# unoshield-v6.net
KiCad netlist of a schematic drawn in EAGLE
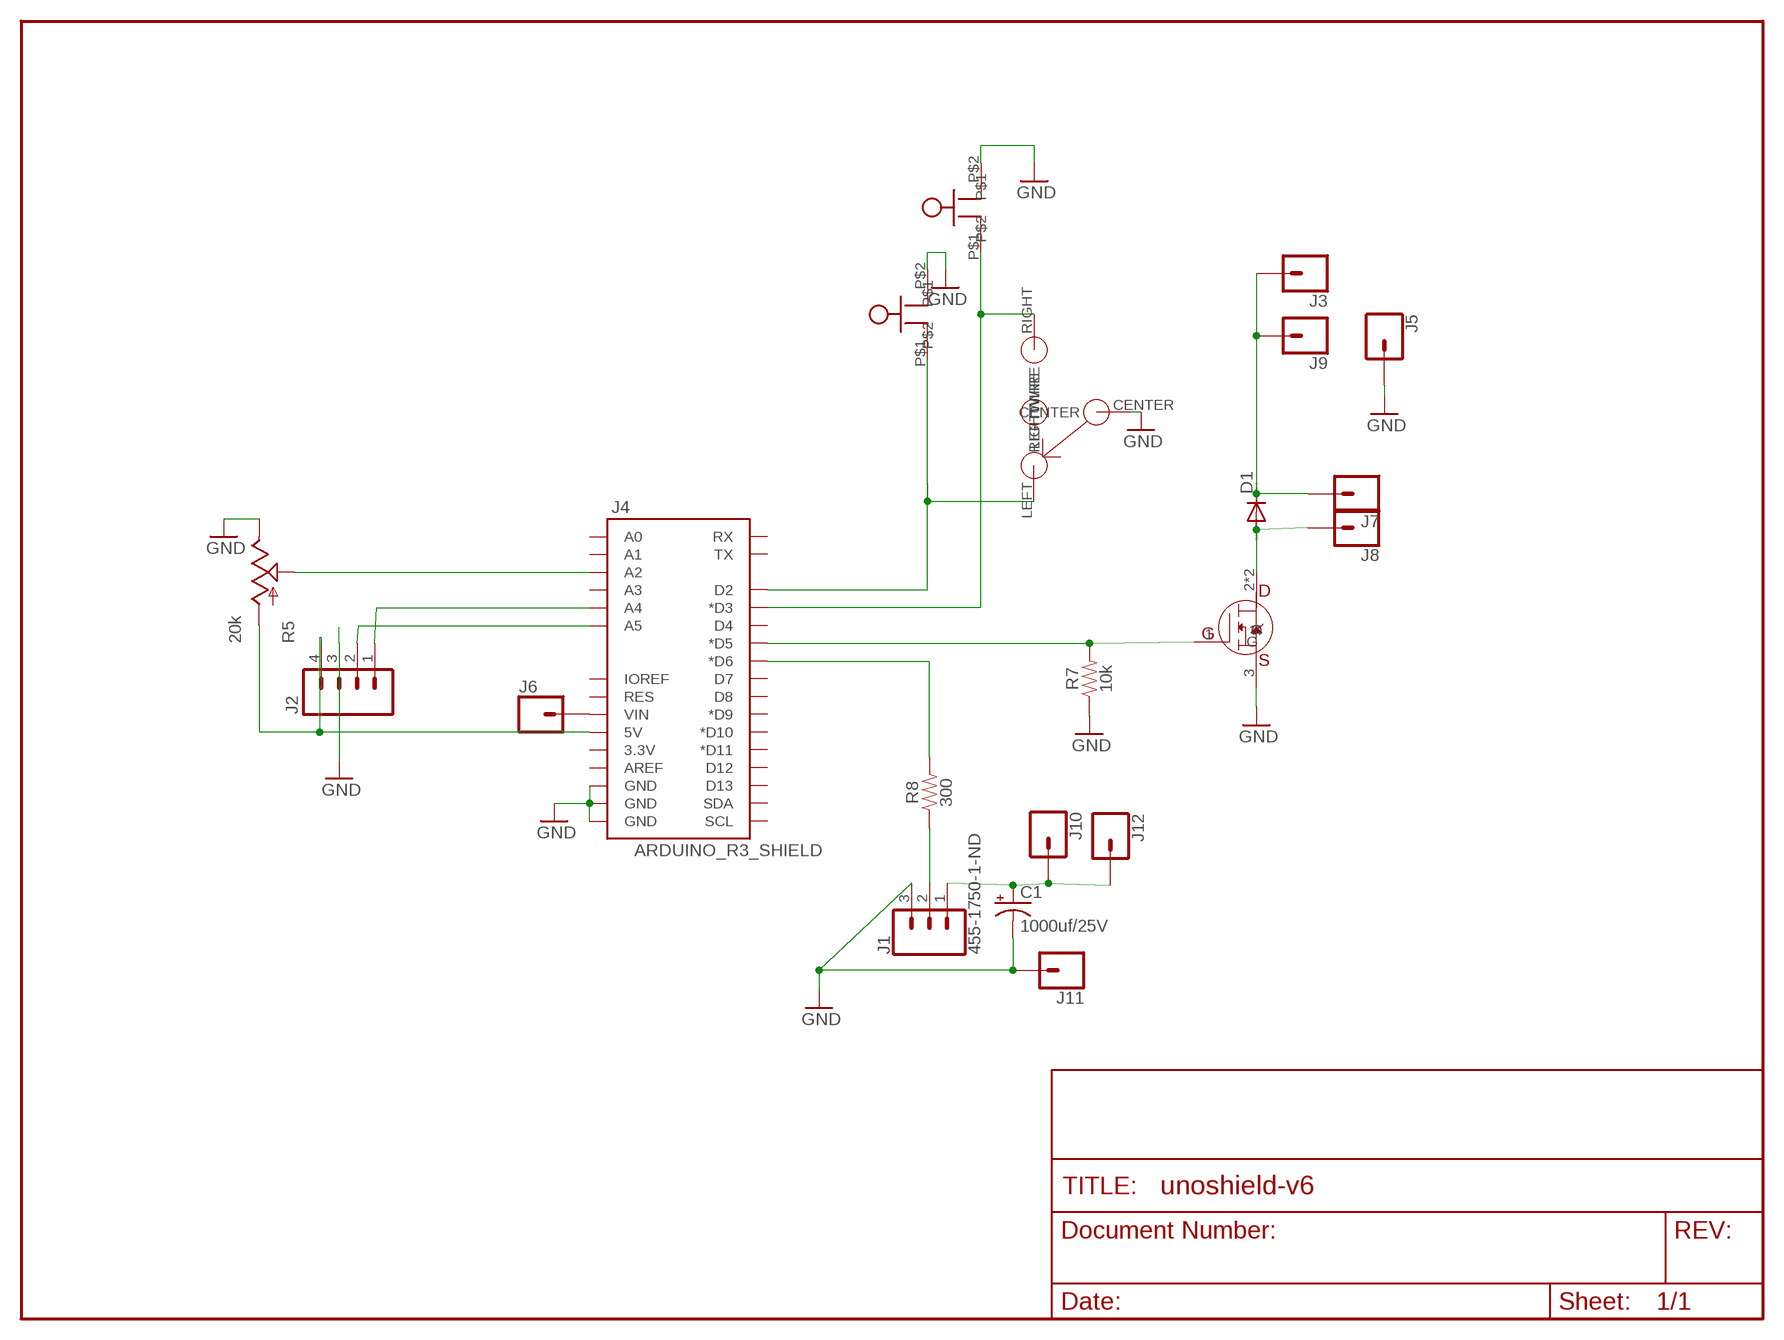
[diagram p0: schematic, sheet 1]

(export (version "E")
  (design (tool "Eeschema 10.0.6"))
  (components
    (comp (ref "C1")
      (value "1000uf/25V")
      (footprint "eagle-import:CPOL-RADIAL-1000UF-25V-KIT")
      (libsource (lib "eagle-import") (part "1000UF-25V(PTH)KIT"))
    )
    (comp (ref "D1")
      (value "DIODE-DO-214AC")
      (footprint "eagle-import:DO-214AC")
      (libsource (lib "eagle-import") (part "DIODE-DO-214AC"))
    )
    (comp (ref "J1")
      (value "455-1750-1-ND")
      (footprint "eagle-import:1X03")
      (libsource (lib "eagle-import") (part "CONN_03"))
    )
    (comp (ref "J2")
      (value "M04PTH")
      (footprint "eagle-import:1X04")
      (libsource (lib "eagle-import") (part "M04PTH"))
    )
    (comp (ref "J3")
      (value "CONN_01PTH_2MM")
      (footprint "eagle-import:1X01_2MM")
      (libsource (lib "eagle-import") (part "CONN_01PTH_2MM"))
    )
    (comp (ref "J4")
      (value "ARDUINO_R3_SHIELD")
      (footprint "eagle-import:UNO_R3_SHIELD")
      (libsource (lib "eagle-import") (part "ARDUINO_R3_SHIELD"))
    )
    (comp (ref "J5")
      (value "CONN_01PTH_2MM")
      (footprint "eagle-import:1X01_2MM")
      (libsource (lib "eagle-import") (part "CONN_01PTH_2MM"))
    )
    (comp (ref "J6")
      (value "CONN_01")
      (footprint "eagle-import:1X01")
      (libsource (lib "eagle-import") (part "CONN_01"))
    )
    (comp (ref "J7")
      (value "CONN_01PTH_2MM")
      (footprint "eagle-import:1X01_2MM")
      (libsource (lib "eagle-import") (part "CONN_01PTH_2MM"))
    )
    (comp (ref "J8")
      (value "CONN_01PTH_2MM")
      (footprint "eagle-import:1X01_2MM")
      (libsource (lib "eagle-import") (part "CONN_01PTH_2MM"))
    )
    (comp (ref "J9")
      (value "CONN_01")
      (footprint "eagle-import:1X01")
      (libsource (lib "eagle-import") (part "CONN_01"))
    )
    (comp (ref "J10")
      (value "CONN_01PTH_2MM")
      (footprint "eagle-import:1X01_2MM")
      (libsource (lib "eagle-import") (part "CONN_01PTH_2MM"))
    )
    (comp (ref "J11")
      (value "CONN_01PTH_2MM")
      (footprint "eagle-import:1X01_2MM")
      (libsource (lib "eagle-import") (part "CONN_01PTH_2MM"))
    )
    (comp (ref "J12")
      (value "CONN_01")
      (footprint "eagle-import:1X01")
      (libsource (lib "eagle-import") (part "CONN_01"))
    )
    (comp (ref "R5")
      (value "20k")
      (footprint "eagle-import:ALPS_POT_KIT")
      (libsource (lib "eagle-import") (part "POTALPS-KIT"))
    )
    (comp (ref "R7")
      (value "10k")
      (footprint "eagle-import:AXIAL-0.3")
      (libsource (lib "eagle-import") (part "10KOHM-HORIZ-1/4W-1%"))
    )
    (comp (ref "R8")
      (value "300")
      (footprint "eagle-import:AXIAL-0.3")
      (libsource (lib "eagle-import") (part "1KOHM-HORIZ-1/4W-5%"))
    )
    (comp (ref "SW1")
      (value "BUTTON")
      (footprint "eagle-import:BUTTON")
      (libsource (lib "eagle-import") (part "BUTTON"))
    )
    (comp (ref "SW2")
      (value "BUTTON")
      (footprint "eagle-import:BUTTON")
      (libsource (lib "eagle-import") (part "BUTTON"))
    )
    (comp (ref "SW3")
      (value "ON-OFF-ON-360-1013-ND")
      (footprint "eagle-import:360-1013-ND")
      (libsource (lib "eagle-import") (part "ON-OFF-ON-360-1013-ND"))
    )
    (comp (ref "U$1")
      (value "IRFL024NPBF")
      (footprint "eagle-import:SOT223")
      (libsource (lib "eagle-import") (part "IRFL024NPBF"))
    )
  )
  (nets
    (net (code "1") (name "GND") (class "Default")
      (node (ref "C1") (pin "-") (pinfunction "-_-") (pintype "passive"))
      (node (ref "J1") (pin "3") (pinfunction "3_3") (pintype "passive"))
      (node (ref "J11") (pin "1") (pinfunction "1_1") (pintype "passive"))
      (node (ref "J2") (pin "3") (pinfunction "3_3") (pintype "passive"))
      (node (ref "J4") (pin "GND@0") (pinfunction "GND_GND@0") (pintype "bidirectional"))
      (node (ref "J4") (pin "GND@1") (pinfunction "GND_GND@1") (pintype "bidirectional"))
      (node (ref "J4") (pin "GND@2") (pinfunction "GND_GND@2") (pintype "bidirectional"))
      (node (ref "J5") (pin "1") (pinfunction "1_1") (pintype "passive"))
      (node (ref "R5") (pin "P$1") (pinfunction "E_P$1") (pintype "passive"))
      (node (ref "R7") (pin "P$1") (pinfunction "1_P$1") (pintype "passive"))
      (node (ref "SW1") (pin "P$2") (pinfunction "P$2_P$2") (pintype "bidirectional"))
      (node (ref "SW2") (pin "P$2") (pinfunction "P$2_P$2") (pintype "bidirectional"))
      (node (ref "SW3") (pin "CENTER") (pinfunction "CENTER_CENTER") (pintype "bidirectional"))
      (node (ref "U$1") (pin "3") (pinfunction "S_3") (pintype "bidirectional"))
    )
    (net (code "2") (name "Net-(C1-Pad+)") (class "Default")
      (node (ref "C1") (pin "+") (pinfunction "+_+") (pintype "passive"))
      (node (ref "J1") (pin "1") (pinfunction "1_1") (pintype "passive"))
      (node (ref "J10") (pin "1") (pinfunction "1_1") (pintype "passive"))
      (node (ref "J12") (pin "1") (pinfunction "1_1") (pintype "passive"))
    )
    (net (code "3") (name "Net-(D1-PadA)") (class "Default")
      (node (ref "D1") (pin "A") (pinfunction "A_A") (pintype "passive"))
      (node (ref "J8") (pin "1") (pinfunction "1_1") (pintype "passive"))
      (node (ref "U$1") (pin "2") (pinfunction "D_2") (pintype "bidirectional"))
      (node (ref "U$1") (pin "4") (pinfunction "D_4") (pintype "bidirectional"))
    )
    (net (code "4") (name "Net-(D1-PadC)") (class "Default")
      (node (ref "D1") (pin "C") (pinfunction "C_C") (pintype "passive"))
      (node (ref "J3") (pin "1") (pinfunction "1_1") (pintype "passive"))
      (node (ref "J7") (pin "1") (pinfunction "1_1") (pintype "passive"))
      (node (ref "J9") (pin "1") (pinfunction "1_1") (pintype "passive"))
    )
    (net (code "5") (name "Net-(J2-Pad1)") (class "Default")
      (node (ref "J2") (pin "1") (pinfunction "1_1") (pintype "passive"))
      (node (ref "J4") (pin "A4") (pinfunction "A4_A4") (pintype "bidirectional"))
    )
    (net (code "6") (name "Net-(J2-Pad2)") (class "Default")
      (node (ref "J2") (pin "2") (pinfunction "2_2") (pintype "passive"))
      (node (ref "J4") (pin "A5") (pinfunction "A5_A5") (pintype "bidirectional"))
    )
    (net (code "7") (name "Net-(J4-*D3)") (class "Default")
      (node (ref "J4") (pin "D3") (pinfunction "*D3_D3") (pintype "bidirectional"))
      (node (ref "SW2") (pin "P$1") (pinfunction "P$1_P$1") (pintype "bidirectional"))
      (node (ref "SW3") (pin "RIGHT") (pinfunction "RIGHTWIRE_RIGHT") (pintype "bidirectional"))
    )
    (net (code "8") (name "Net-(J4-*D5)") (class "Default")
      (node (ref "J4") (pin "D5") (pinfunction "*D5_D5") (pintype "bidirectional"))
      (node (ref "R7") (pin "P$2") (pinfunction "2_P$2") (pintype "passive"))
      (node (ref "U$1") (pin "1") (pinfunction "G_1") (pintype "bidirectional"))
    )
    (net (code "9") (name "Net-(J4-*D6)") (class "Default")
      (node (ref "J4") (pin "D6") (pinfunction "*D6_D6") (pintype "bidirectional"))
      (node (ref "R8") (pin "P$2") (pinfunction "2_P$2") (pintype "passive"))
    )
    (net (code "10") (name "Net-(J4-PadVIN)") (class "Default")
      (node (ref "J4") (pin "VIN") (pinfunction "VIN_VIN") (pintype "bidirectional"))
      (node (ref "J6") (pin "1") (pinfunction "1_1") (pintype "passive"))
    )
    (net (code "11") (name "Net-(R5-A)") (class "Default")
      (node (ref "J2") (pin "4") (pinfunction "4_4") (pintype "passive"))
      (node (ref "J4") (pin "5V") (pinfunction "5V_5V") (pintype "bidirectional"))
      (node (ref "R5") (pin "P$3") (pinfunction "A_P$3") (pintype "passive"))
    )
    (net (code "12") (name "Net-(R5-S)") (class "Default")
      (node (ref "J4") (pin "A2") (pinfunction "A2_A2") (pintype "bidirectional"))
      (node (ref "R5") (pin "P$2") (pinfunction "S_P$2") (pintype "passive"))
    )
    (net (code "13") (name "Net-(R8-1)") (class "Default")
      (node (ref "J1") (pin "2") (pinfunction "2_2") (pintype "passive"))
      (node (ref "R8") (pin "P$1") (pinfunction "1_P$1") (pintype "passive"))
    )
    (net (code "14") (name "Net-(SW3-LEFTWIRE)") (class "Default")
      (node (ref "J4") (pin "D2") (pinfunction "D2_D2") (pintype "bidirectional"))
      (node (ref "SW1") (pin "P$1") (pinfunction "P$1_P$1") (pintype "bidirectional"))
      (node (ref "SW3") (pin "LEFT") (pinfunction "LEFTWIRE_LEFT") (pintype "bidirectional"))
    )
    (net (code "15") (name "unconnected-(J4-*D9-PadD9)") (class "Default")
      (node (ref "J4") (pin "D9") (pinfunction "*D9_D9") (pintype "bidirectional"))
    )
    (net (code "16") (name "unconnected-(J4-*D10-PadD10)") (class "Default")
      (node (ref "J4") (pin "D10") (pinfunction "*D10_D10") (pintype "bidirectional"))
    )
    (net (code "17") (name "unconnected-(J4-*D11-PadD11)") (class "Default")
      (node (ref "J4") (pin "D11") (pinfunction "*D11_D11") (pintype "bidirectional"))
    )
    (net (code "18") (name "unconnected-(J4-Pad3.3V)") (class "Default")
      (node (ref "J4") (pin "3.3V") (pinfunction "3.3V_3.3V") (pintype "bidirectional"))
    )
    (net (code "19") (name "unconnected-(J4-PadA0)") (class "Default")
      (node (ref "J4") (pin "A0") (pinfunction "A0_A0") (pintype "bidirectional"))
    )
    (net (code "20") (name "unconnected-(J4-PadA1)") (class "Default")
      (node (ref "J4") (pin "A1") (pinfunction "A1_A1") (pintype "bidirectional"))
    )
    (net (code "21") (name "unconnected-(J4-PadA3)") (class "Default")
      (node (ref "J4") (pin "A3") (pinfunction "A3_A3") (pintype "bidirectional"))
    )
    (net (code "22") (name "unconnected-(J4-PadAREF)") (class "Default")
      (node (ref "J4") (pin "AREF") (pinfunction "AREF_AREF") (pintype "bidirectional"))
    )
    (net (code "23") (name "unconnected-(J4-PadD4)") (class "Default")
      (node (ref "J4") (pin "D4") (pinfunction "D4_D4") (pintype "bidirectional"))
    )
    (net (code "24") (name "unconnected-(J4-PadD7)") (class "Default")
      (node (ref "J4") (pin "D7") (pinfunction "D7_D7") (pintype "bidirectional"))
    )
    (net (code "25") (name "unconnected-(J4-PadD8)") (class "Default")
      (node (ref "J4") (pin "D8") (pinfunction "D8_D8") (pintype "bidirectional"))
    )
    (net (code "26") (name "unconnected-(J4-PadD12)") (class "Default")
      (node (ref "J4") (pin "D12") (pinfunction "D12_D12") (pintype "bidirectional"))
    )
    (net (code "27") (name "unconnected-(J4-PadD13)") (class "Default")
      (node (ref "J4") (pin "D13") (pinfunction "D13_D13") (pintype "bidirectional"))
    )
    (net (code "28") (name "unconnected-(J4-PadIOREF)") (class "Default")
      (node (ref "J4") (pin "IOREF") (pinfunction "IOREF_IOREF") (pintype "bidirectional"))
    )
    (net (code "29") (name "unconnected-(J4-PadRES)") (class "Default")
      (node (ref "J4") (pin "RES") (pinfunction "RES_RES") (pintype "bidirectional"))
    )
    (net (code "30") (name "unconnected-(J4-PadRX)") (class "Default")
      (node (ref "J4") (pin "RX") (pinfunction "RX_RX") (pintype "bidirectional"))
    )
    (net (code "31") (name "unconnected-(J4-PadSCL)") (class "Default")
      (node (ref "J4") (pin "SCL") (pinfunction "SCL_SCL") (pintype "bidirectional"))
    )
    (net (code "32") (name "unconnected-(J4-PadSDA)") (class "Default")
      (node (ref "J4") (pin "SDA") (pinfunction "SDA_SDA") (pintype "bidirectional"))
    )
    (net (code "33") (name "unconnected-(J4-PadTX)") (class "Default")
      (node (ref "J4") (pin "TX") (pinfunction "TX_TX") (pintype "bidirectional"))
    )
  )
)
